# TH3122_to_ARDUINO.net
KiCad netlist of a schematic drawn in EAGLE
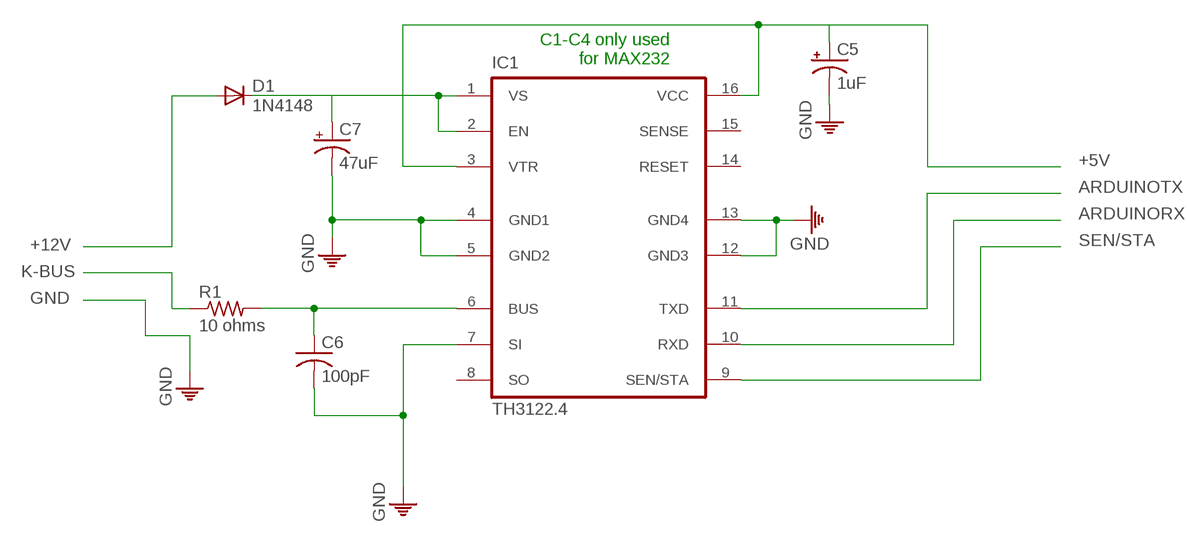
[diagram p0: schematic, sheet 1]

(export (version "E")
  (design (tool "Eeschema 10.0.6"))
  (components
    (comp (ref "C5")
      (value "1uF")
      (footprint "eagle-import:PANASONIC_A")
      (libsource (lib "eagle-import") (part "CPOL-USA"))
    )
    (comp (ref "C6")
      (value "100pF")
      (footprint "eagle-import:C025-030X050")
      (libsource (lib "eagle-import") (part "C-US025-030X050"))
    )
    (comp (ref "C7")
      (value "47uF")
      (footprint "eagle-import:PANASONIC_A")
      (libsource (lib "eagle-import") (part "CPOL-USA"))
    )
    (comp (ref "D1")
      (value "1N4148")
      (footprint "eagle-import:DO35-10")
      (libsource (lib "eagle-import") (part "1N4148DO35-10"))
    )
    (comp (ref "IC1")
      (value "TH3122.4")
      (footprint "eagle-import:TH3122")
      (libsource (lib "eagle-import") (part "TH3122.4"))
    )
    (comp (ref "R1")
      (value "10 ohms")
      (footprint "eagle-import:0204_5")
      (libsource (lib "eagle-import") (part "R-US_0204/5"))
    )
  )
  (nets
    (net (code "1") (name "/+5V") (class "Default")
      (node (ref "C5") (pin "+") (pinfunction "+_+") (pintype "passive"))
      (node (ref "IC1") (pin "16") (pinfunction "VCC_16") (pintype "output"))
      (node (ref "IC1") (pin "3") (pinfunction "VTR_3") (pintype "input"))
    )
    (net (code "2") (name "/+12V") (class "Default")
      (node (ref "D1") (pin "A") (pinfunction "A_A") (pintype "passive"))
    )
    (net (code "3") (name "/ARDUINORX") (class "Default")
      (node (ref "IC1") (pin "10") (pinfunction "RXD_10") (pintype "output"))
    )
    (net (code "4") (name "/ARDUINOTX") (class "Default")
      (node (ref "IC1") (pin "11") (pinfunction "TXD_11") (pintype "input"))
    )
    (net (code "5") (name "/K-BUS") (class "Default")
      (node (ref "R1") (pin "1") (pinfunction "1_1") (pintype "passive"))
    )
    (net (code "6") (name "/SEN{slash}STA") (class "Default")
      (node (ref "IC1") (pin "9") (pinfunction "SEN/STA_9") (pintype "bidirectional"))
    )
    (net (code "7") (name "GND") (class "Default")
      (node (ref "C5") (pin "-") (pinfunction "-_-") (pintype "passive"))
      (node (ref "C6") (pin "2") (pinfunction "2_2") (pintype "passive"))
      (node (ref "C7") (pin "-") (pinfunction "-_-") (pintype "passive"))
      (node (ref "IC1") (pin "12") (pinfunction "GND3_12") (pintype "power_in"))
      (node (ref "IC1") (pin "13") (pinfunction "GND4_13") (pintype "power_in"))
      (node (ref "IC1") (pin "4") (pinfunction "GND1_4") (pintype "power_in"))
      (node (ref "IC1") (pin "5") (pinfunction "GND2_5") (pintype "power_in"))
      (node (ref "IC1") (pin "7") (pinfunction "SI_7") (pintype "input"))
    )
    (net (code "8") (name "Net-(IC1-BUS)") (class "Default")
      (node (ref "C6") (pin "1") (pinfunction "1_1") (pintype "passive"))
      (node (ref "IC1") (pin "6") (pinfunction "BUS_6") (pintype "bidirectional"))
      (node (ref "R1") (pin "2") (pinfunction "2_2") (pintype "passive"))
    )
    (net (code "9") (name "Net-(IC1-EN)") (class "Default")
      (node (ref "C7") (pin "+") (pinfunction "+_+") (pintype "passive"))
      (node (ref "D1") (pin "C") (pinfunction "C_C") (pintype "passive"))
      (node (ref "IC1") (pin "1") (pinfunction "VS_1") (pintype "power_in"))
      (node (ref "IC1") (pin "2") (pinfunction "EN_2") (pintype "input"))
    )
    (net (code "10") (name "unconnected-(IC1-RESET-Pad14)") (class "Default")
      (node (ref "IC1") (pin "14") (pinfunction "RESET_14") (pintype "input"))
    )
    (net (code "11") (name "unconnected-(IC1-SENSE-Pad15)") (class "Default")
      (node (ref "IC1") (pin "15") (pinfunction "SENSE_15") (pintype "output"))
    )
    (net (code "12") (name "unconnected-(IC1-SO-Pad8)") (class "Default")
      (node (ref "IC1") (pin "8") (pinfunction "SO_8") (pintype "output"))
    )
  )
)
